# driver3.net
KiCad netlist of a schematic drawn in EAGLE
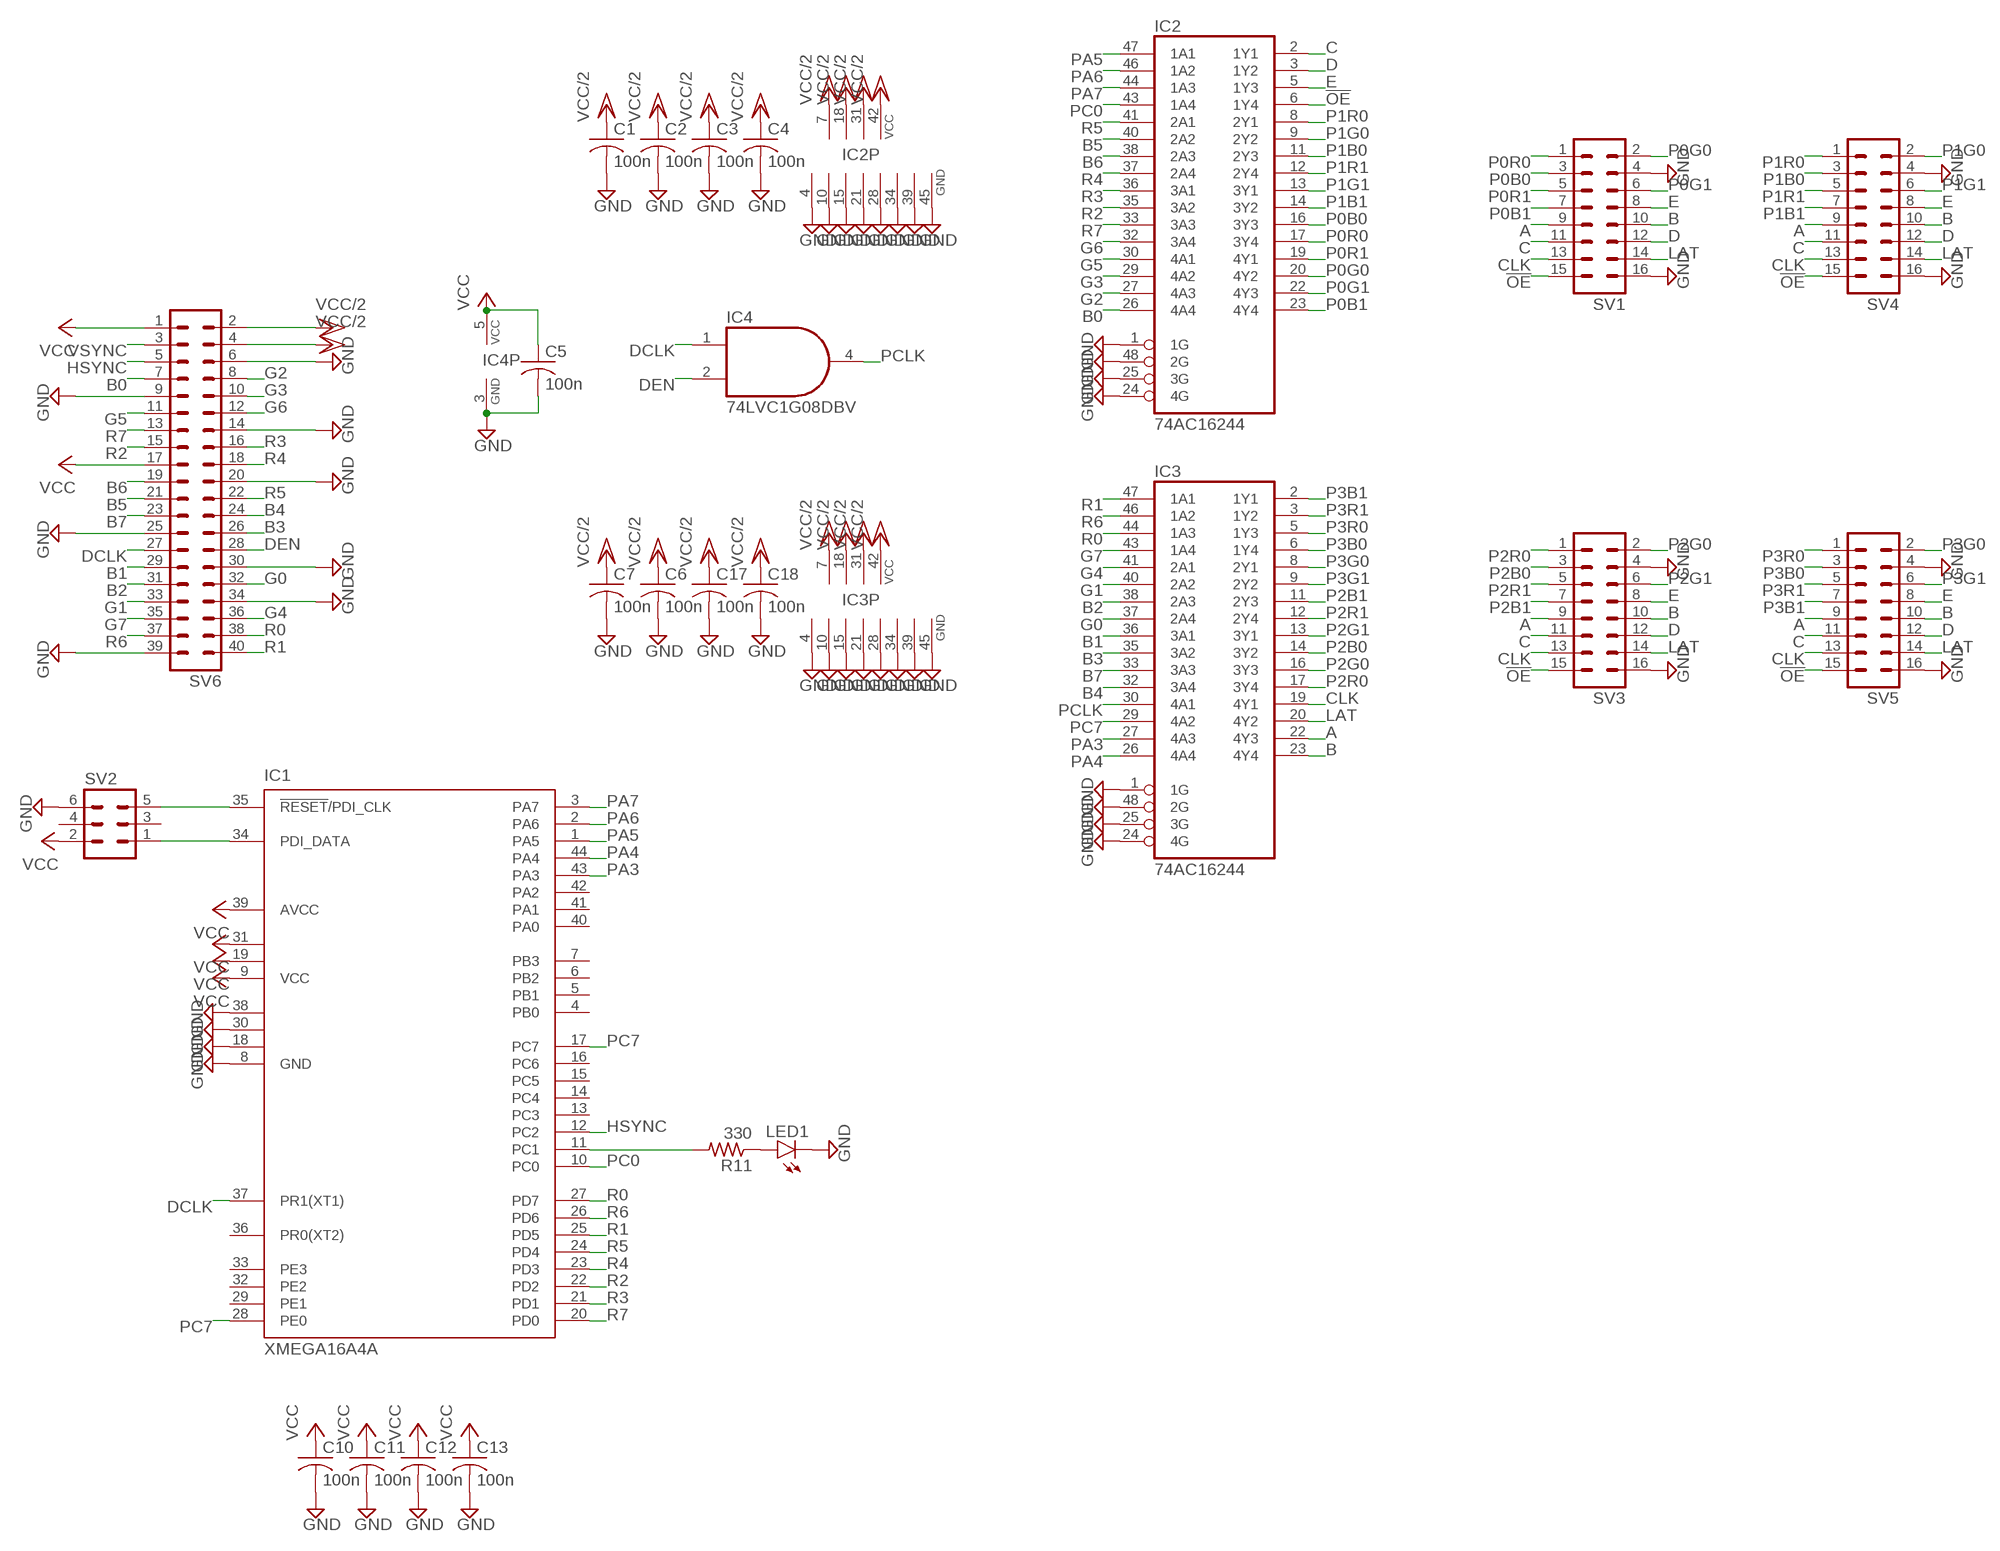
[diagram p0: schematic, sheet 1]

(export (version "E")
  (design (tool "Eeschema 10.0.6"))
  (components
    (comp (ref "C1")
      (value "100n")
      (footprint "eagle-import:C0402")
      (libsource (lib "eagle-import") (part "C-USC0402"))
    )
    (comp (ref "C2")
      (value "100n")
      (footprint "eagle-import:C0402")
      (libsource (lib "eagle-import") (part "C-USC0402"))
    )
    (comp (ref "C3")
      (value "100n")
      (footprint "eagle-import:C0402")
      (libsource (lib "eagle-import") (part "C-USC0402"))
    )
    (comp (ref "C4")
      (value "100n")
      (footprint "eagle-import:C0402")
      (libsource (lib "eagle-import") (part "C-USC0402"))
    )
    (comp (ref "C5")
      (value "100n")
      (footprint "eagle-import:C0402")
      (libsource (lib "eagle-import") (part "C-USC0402"))
    )
    (comp (ref "C6")
      (value "100n")
      (footprint "eagle-import:C0402")
      (libsource (lib "eagle-import") (part "C-USC0402"))
    )
    (comp (ref "C7")
      (value "100n")
      (footprint "eagle-import:C0402")
      (libsource (lib "eagle-import") (part "C-USC0402"))
    )
    (comp (ref "C10")
      (value "100n")
      (footprint "eagle-import:C0402")
      (libsource (lib "eagle-import") (part "C-USC0402"))
    )
    (comp (ref "C11")
      (value "100n")
      (footprint "eagle-import:C0402")
      (libsource (lib "eagle-import") (part "C-USC0402"))
    )
    (comp (ref "C12")
      (value "100n")
      (footprint "eagle-import:C0402")
      (libsource (lib "eagle-import") (part "C-USC0402"))
    )
    (comp (ref "C13")
      (value "100n")
      (footprint "eagle-import:C0402")
      (libsource (lib "eagle-import") (part "C-USC0402"))
    )
    (comp (ref "C17")
      (value "100n")
      (footprint "eagle-import:C0402")
      (libsource (lib "eagle-import") (part "C-USC0402"))
    )
    (comp (ref "C18")
      (value "100n")
      (footprint "eagle-import:C0402")
      (libsource (lib "eagle-import") (part "C-USC0402"))
    )
    (comp (ref "IC1")
      (value "XMEGA16A4A")
      (footprint "eagle-import:TQFP44")
      (libsource (lib "eagle-import") (part "XMEGA16A4A"))
    )
    (comp (ref "IC2")
      (value "74AC16244")
      (footprint "eagle-import:SSOP48DL")
      (libsource (lib "eagle-import") (part "74AC16244"))
    )
    (comp (ref "IC3")
      (value "74AC16244")
      (footprint "eagle-import:SSOP48DL")
      (libsource (lib "eagle-import") (part "74AC16244"))
    )
    (comp (ref "IC4")
      (value "74LVC1G08DBV")
      (footprint "eagle-import:SOT23-5")
      (libsource (lib "eagle-import") (part "741G08DBVLVC"))
    )
    (comp (ref "LED1")
      (value "LEDCHIPLED_0805")
      (footprint "eagle-import:CHIPLED_0805")
      (libsource (lib "eagle-import") (part "LEDCHIPLED_0805"))
    )
    (comp (ref "R11")
      (value "330")
      (footprint "eagle-import:R0402")
      (libsource (lib "eagle-import") (part "R-US_R0402"))
    )
    (comp (ref "SV1")
      (value "MA08-2")
      (footprint "eagle-import:MA08-2")
      (libsource (lib "eagle-import") (part "MA08-2"))
    )
    (comp (ref "SV2")
      (value "MA03-2")
      (footprint "eagle-import:MA03-2")
      (libsource (lib "eagle-import") (part "MA03-2"))
    )
    (comp (ref "SV3")
      (value "MA08-2")
      (footprint "eagle-import:MA08-2")
      (libsource (lib "eagle-import") (part "MA08-2"))
    )
    (comp (ref "SV4")
      (value "MA08-2")
      (footprint "eagle-import:MA08-2")
      (libsource (lib "eagle-import") (part "MA08-2"))
    )
    (comp (ref "SV5")
      (value "MA08-2")
      (footprint "eagle-import:MA08-2")
      (libsource (lib "eagle-import") (part "MA08-2"))
    )
    (comp (ref "SV6")
      (value "MA20-2")
      (footprint "eagle-import:MA20-2")
      (libsource (lib "eagle-import") (part "MA20-2"))
    )
  )
  (nets
    (net (code "1") (name "/A") (class "Default")
      (node (ref "IC3") (pin "22") (pinfunction "4Y3_22") (pintype "tri_state"))
      (node (ref "SV1") (pin "9") (pinfunction "9_9") (pintype "passive"))
      (node (ref "SV3") (pin "9") (pinfunction "9_9") (pintype "passive"))
      (node (ref "SV4") (pin "9") (pinfunction "9_9") (pintype "passive"))
      (node (ref "SV5") (pin "9") (pinfunction "9_9") (pintype "passive"))
    )
    (net (code "2") (name "/B") (class "Default")
      (node (ref "IC3") (pin "23") (pinfunction "4Y4_23") (pintype "tri_state"))
      (node (ref "SV1") (pin "10") (pinfunction "10_10") (pintype "passive"))
      (node (ref "SV3") (pin "10") (pinfunction "10_10") (pintype "passive"))
      (node (ref "SV4") (pin "10") (pinfunction "10_10") (pintype "passive"))
      (node (ref "SV5") (pin "10") (pinfunction "10_10") (pintype "passive"))
    )
    (net (code "3") (name "/B0") (class "Default")
      (node (ref "IC2") (pin "26") (pinfunction "4A4_26") (pintype "input"))
      (node (ref "SV6") (pin "7") (pinfunction "7_7") (pintype "passive"))
    )
    (net (code "4") (name "/B1") (class "Default")
      (node (ref "IC3") (pin "36") (pinfunction "3A1_36") (pintype "input"))
      (node (ref "SV6") (pin "29") (pinfunction "29_29") (pintype "passive"))
    )
    (net (code "5") (name "/B2") (class "Default")
      (node (ref "IC3") (pin "38") (pinfunction "2A3_38") (pintype "input"))
      (node (ref "SV6") (pin "31") (pinfunction "31_31") (pintype "passive"))
    )
    (net (code "6") (name "/B3") (class "Default")
      (node (ref "IC3") (pin "35") (pinfunction "3A2_35") (pintype "input"))
      (node (ref "SV6") (pin "26") (pinfunction "26_26") (pintype "passive"))
    )
    (net (code "7") (name "/B4") (class "Default")
      (node (ref "IC3") (pin "32") (pinfunction "3A4_32") (pintype "input"))
      (node (ref "SV6") (pin "24") (pinfunction "24_24") (pintype "passive"))
    )
    (net (code "8") (name "/B5") (class "Default")
      (node (ref "IC2") (pin "40") (pinfunction "2A2_40") (pintype "input"))
      (node (ref "SV6") (pin "21") (pinfunction "21_21") (pintype "passive"))
    )
    (net (code "9") (name "/B6") (class "Default")
      (node (ref "IC2") (pin "38") (pinfunction "2A3_38") (pintype "input"))
      (node (ref "SV6") (pin "19") (pinfunction "19_19") (pintype "passive"))
    )
    (net (code "10") (name "/B7") (class "Default")
      (node (ref "IC3") (pin "33") (pinfunction "3A3_33") (pintype "input"))
      (node (ref "SV6") (pin "23") (pinfunction "23_23") (pintype "passive"))
    )
    (net (code "11") (name "/C") (class "Default")
      (node (ref "IC2") (pin "2") (pinfunction "1Y1_2") (pintype "tri_state"))
      (node (ref "SV1") (pin "11") (pinfunction "11_11") (pintype "passive"))
      (node (ref "SV3") (pin "11") (pinfunction "11_11") (pintype "passive"))
      (node (ref "SV4") (pin "11") (pinfunction "11_11") (pintype "passive"))
      (node (ref "SV5") (pin "11") (pinfunction "11_11") (pintype "passive"))
    )
    (net (code "12") (name "/CLK") (class "Default")
      (node (ref "IC3") (pin "19") (pinfunction "4Y1_19") (pintype "tri_state"))
      (node (ref "SV1") (pin "13") (pinfunction "13_13") (pintype "passive"))
      (node (ref "SV3") (pin "13") (pinfunction "13_13") (pintype "passive"))
      (node (ref "SV4") (pin "13") (pinfunction "13_13") (pintype "passive"))
      (node (ref "SV5") (pin "13") (pinfunction "13_13") (pintype "passive"))
    )
    (net (code "13") (name "/D") (class "Default")
      (node (ref "IC2") (pin "3") (pinfunction "1Y2_3") (pintype "tri_state"))
      (node (ref "SV1") (pin "12") (pinfunction "12_12") (pintype "passive"))
      (node (ref "SV3") (pin "12") (pinfunction "12_12") (pintype "passive"))
      (node (ref "SV4") (pin "12") (pinfunction "12_12") (pintype "passive"))
      (node (ref "SV5") (pin "12") (pinfunction "12_12") (pintype "passive"))
    )
    (net (code "14") (name "/DCLK") (class "Default")
      (node (ref "IC1") (pin "37") (pinfunction "PR1(XT1)_37") (pintype "bidirectional"))
      (node (ref "IC4") (pin "1") (pinfunction "I0_1") (pintype "input"))
      (node (ref "SV6") (pin "27") (pinfunction "27_27") (pintype "passive"))
    )
    (net (code "15") (name "/DEN") (class "Default")
      (node (ref "IC4") (pin "2") (pinfunction "I1_2") (pintype "input"))
      (node (ref "SV6") (pin "28") (pinfunction "28_28") (pintype "passive"))
    )
    (net (code "16") (name "/E") (class "Default")
      (node (ref "IC2") (pin "5") (pinfunction "1Y3_5") (pintype "tri_state"))
      (node (ref "SV1") (pin "8") (pinfunction "8_8") (pintype "passive"))
      (node (ref "SV3") (pin "8") (pinfunction "8_8") (pintype "passive"))
      (node (ref "SV4") (pin "8") (pinfunction "8_8") (pintype "passive"))
      (node (ref "SV5") (pin "8") (pinfunction "8_8") (pintype "passive"))
    )
    (net (code "17") (name "/G0") (class "Default")
      (node (ref "IC3") (pin "37") (pinfunction "2A4_37") (pintype "input"))
      (node (ref "SV6") (pin "32") (pinfunction "32_32") (pintype "passive"))
    )
    (net (code "18") (name "/G1") (class "Default")
      (node (ref "IC3") (pin "40") (pinfunction "2A2_40") (pintype "input"))
      (node (ref "SV6") (pin "33") (pinfunction "33_33") (pintype "passive"))
    )
    (net (code "19") (name "/G2") (class "Default")
      (node (ref "IC2") (pin "27") (pinfunction "4A3_27") (pintype "input"))
      (node (ref "SV6") (pin "8") (pinfunction "8_8") (pintype "passive"))
    )
    (net (code "20") (name "/G3") (class "Default")
      (node (ref "IC2") (pin "29") (pinfunction "4A2_29") (pintype "input"))
      (node (ref "SV6") (pin "10") (pinfunction "10_10") (pintype "passive"))
    )
    (net (code "21") (name "/G4") (class "Default")
      (node (ref "IC3") (pin "41") (pinfunction "2A1_41") (pintype "input"))
      (node (ref "SV6") (pin "36") (pinfunction "36_36") (pintype "passive"))
    )
    (net (code "22") (name "/G5") (class "Default")
      (node (ref "IC2") (pin "30") (pinfunction "4A1_30") (pintype "input"))
      (node (ref "SV6") (pin "11") (pinfunction "11_11") (pintype "passive"))
    )
    (net (code "23") (name "/G6") (class "Default")
      (node (ref "IC2") (pin "32") (pinfunction "3A4_32") (pintype "input"))
      (node (ref "SV6") (pin "12") (pinfunction "12_12") (pintype "passive"))
    )
    (net (code "24") (name "/G7") (class "Default")
      (node (ref "IC3") (pin "43") (pinfunction "1A4_43") (pintype "input"))
      (node (ref "SV6") (pin "35") (pinfunction "35_35") (pintype "passive"))
    )
    (net (code "25") (name "/HSYNC") (class "Default")
      (node (ref "IC1") (pin "12") (pinfunction "PC2_12") (pintype "bidirectional"))
      (node (ref "SV6") (pin "5") (pinfunction "5_5") (pintype "passive"))
    )
    (net (code "26") (name "/LAT") (class "Default")
      (node (ref "IC3") (pin "20") (pinfunction "4Y2_20") (pintype "tri_state"))
      (node (ref "SV1") (pin "14") (pinfunction "14_14") (pintype "passive"))
      (node (ref "SV3") (pin "14") (pinfunction "14_14") (pintype "passive"))
      (node (ref "SV4") (pin "14") (pinfunction "14_14") (pintype "passive"))
      (node (ref "SV5") (pin "14") (pinfunction "14_14") (pintype "passive"))
    )
    (net (code "27") (name "/P0B0") (class "Default")
      (node (ref "IC2") (pin "16") (pinfunction "3Y3_16") (pintype "tri_state"))
      (node (ref "SV1") (pin "3") (pinfunction "3_3") (pintype "passive"))
    )
    (net (code "28") (name "/P0B1") (class "Default")
      (node (ref "IC2") (pin "23") (pinfunction "4Y4_23") (pintype "tri_state"))
      (node (ref "SV1") (pin "7") (pinfunction "7_7") (pintype "passive"))
    )
    (net (code "29") (name "/P0G0") (class "Default")
      (node (ref "IC2") (pin "20") (pinfunction "4Y2_20") (pintype "tri_state"))
      (node (ref "SV1") (pin "2") (pinfunction "2_2") (pintype "passive"))
    )
    (net (code "30") (name "/P0G1") (class "Default")
      (node (ref "IC2") (pin "22") (pinfunction "4Y3_22") (pintype "tri_state"))
      (node (ref "SV1") (pin "6") (pinfunction "6_6") (pintype "passive"))
    )
    (net (code "31") (name "/P0R0") (class "Default")
      (node (ref "IC2") (pin "17") (pinfunction "3Y4_17") (pintype "tri_state"))
      (node (ref "SV1") (pin "1") (pinfunction "1_1") (pintype "passive"))
    )
    (net (code "32") (name "/P0R1") (class "Default")
      (node (ref "IC2") (pin "19") (pinfunction "4Y1_19") (pintype "tri_state"))
      (node (ref "SV1") (pin "5") (pinfunction "5_5") (pintype "passive"))
    )
    (net (code "33") (name "/P1B0") (class "Default")
      (node (ref "IC2") (pin "11") (pinfunction "2Y3_11") (pintype "tri_state"))
      (node (ref "SV4") (pin "3") (pinfunction "3_3") (pintype "passive"))
    )
    (net (code "34") (name "/P1B1") (class "Default")
      (node (ref "IC2") (pin "14") (pinfunction "3Y2_14") (pintype "tri_state"))
      (node (ref "SV4") (pin "7") (pinfunction "7_7") (pintype "passive"))
    )
    (net (code "35") (name "/P1G0") (class "Default")
      (node (ref "IC2") (pin "9") (pinfunction "2Y2_9") (pintype "tri_state"))
      (node (ref "SV4") (pin "2") (pinfunction "2_2") (pintype "passive"))
    )
    (net (code "36") (name "/P1G1") (class "Default")
      (node (ref "IC2") (pin "13") (pinfunction "3Y1_13") (pintype "tri_state"))
      (node (ref "SV4") (pin "6") (pinfunction "6_6") (pintype "passive"))
    )
    (net (code "37") (name "/P1R0") (class "Default")
      (node (ref "IC2") (pin "8") (pinfunction "2Y1_8") (pintype "tri_state"))
      (node (ref "SV4") (pin "1") (pinfunction "1_1") (pintype "passive"))
    )
    (net (code "38") (name "/P1R1") (class "Default")
      (node (ref "IC2") (pin "12") (pinfunction "2Y4_12") (pintype "tri_state"))
      (node (ref "SV4") (pin "5") (pinfunction "5_5") (pintype "passive"))
    )
    (net (code "39") (name "/P2B0") (class "Default")
      (node (ref "IC3") (pin "14") (pinfunction "3Y2_14") (pintype "tri_state"))
      (node (ref "SV3") (pin "3") (pinfunction "3_3") (pintype "passive"))
    )
    (net (code "40") (name "/P2B1") (class "Default")
      (node (ref "IC3") (pin "11") (pinfunction "2Y3_11") (pintype "tri_state"))
      (node (ref "SV3") (pin "7") (pinfunction "7_7") (pintype "passive"))
    )
    (net (code "41") (name "/P2G0") (class "Default")
      (node (ref "IC3") (pin "16") (pinfunction "3Y3_16") (pintype "tri_state"))
      (node (ref "SV3") (pin "2") (pinfunction "2_2") (pintype "passive"))
    )
    (net (code "42") (name "/P2G1") (class "Default")
      (node (ref "IC3") (pin "13") (pinfunction "3Y1_13") (pintype "tri_state"))
      (node (ref "SV3") (pin "6") (pinfunction "6_6") (pintype "passive"))
    )
    (net (code "43") (name "/P2R0") (class "Default")
      (node (ref "IC3") (pin "17") (pinfunction "3Y4_17") (pintype "tri_state"))
      (node (ref "SV3") (pin "1") (pinfunction "1_1") (pintype "passive"))
    )
    (net (code "44") (name "/P2R1") (class "Default")
      (node (ref "IC3") (pin "12") (pinfunction "2Y4_12") (pintype "tri_state"))
      (node (ref "SV3") (pin "5") (pinfunction "5_5") (pintype "passive"))
    )
    (net (code "45") (name "/P3B0") (class "Default")
      (node (ref "IC3") (pin "6") (pinfunction "1Y4_6") (pintype "tri_state"))
      (node (ref "SV5") (pin "3") (pinfunction "3_3") (pintype "passive"))
    )
    (net (code "46") (name "/P3B1") (class "Default")
      (node (ref "IC3") (pin "2") (pinfunction "1Y1_2") (pintype "tri_state"))
      (node (ref "SV5") (pin "7") (pinfunction "7_7") (pintype "passive"))
    )
    (net (code "47") (name "/P3G0") (class "Default")
      (node (ref "IC3") (pin "8") (pinfunction "2Y1_8") (pintype "tri_state"))
      (node (ref "SV5") (pin "2") (pinfunction "2_2") (pintype "passive"))
    )
    (net (code "48") (name "/P3G1") (class "Default")
      (node (ref "IC3") (pin "9") (pinfunction "2Y2_9") (pintype "tri_state"))
      (node (ref "SV5") (pin "6") (pinfunction "6_6") (pintype "passive"))
    )
    (net (code "49") (name "/P3R0") (class "Default")
      (node (ref "IC3") (pin "5") (pinfunction "1Y3_5") (pintype "tri_state"))
      (node (ref "SV5") (pin "1") (pinfunction "1_1") (pintype "passive"))
    )
    (net (code "50") (name "/P3R1") (class "Default")
      (node (ref "IC3") (pin "3") (pinfunction "1Y2_3") (pintype "tri_state"))
      (node (ref "SV5") (pin "5") (pinfunction "5_5") (pintype "passive"))
    )
    (net (code "51") (name "/PA3") (class "Default")
      (node (ref "IC1") (pin "43") (pinfunction "PA3_43") (pintype "bidirectional"))
      (node (ref "IC3") (pin "27") (pinfunction "4A3_27") (pintype "input"))
    )
    (net (code "52") (name "/PA4") (class "Default")
      (node (ref "IC1") (pin "44") (pinfunction "PA4_44") (pintype "bidirectional"))
      (node (ref "IC3") (pin "26") (pinfunction "4A4_26") (pintype "input"))
    )
    (net (code "53") (name "/PA5") (class "Default")
      (node (ref "IC1") (pin "1") (pinfunction "PA5_1") (pintype "bidirectional"))
      (node (ref "IC2") (pin "47") (pinfunction "1A1_47") (pintype "input"))
    )
    (net (code "54") (name "/PA6") (class "Default")
      (node (ref "IC1") (pin "2") (pinfunction "PA6_2") (pintype "bidirectional"))
      (node (ref "IC2") (pin "46") (pinfunction "1A2_46") (pintype "input"))
    )
    (net (code "55") (name "/PA7") (class "Default")
      (node (ref "IC1") (pin "3") (pinfunction "PA7_3") (pintype "bidirectional"))
      (node (ref "IC2") (pin "44") (pinfunction "1A3_44") (pintype "input"))
    )
    (net (code "56") (name "/PC0") (class "Default")
      (node (ref "IC1") (pin "10") (pinfunction "PC0_10") (pintype "bidirectional"))
      (node (ref "IC2") (pin "43") (pinfunction "1A4_43") (pintype "input"))
    )
    (net (code "57") (name "/PC7") (class "Default")
      (node (ref "IC1") (pin "17") (pinfunction "PC7_17") (pintype "bidirectional"))
      (node (ref "IC1") (pin "28") (pinfunction "PE0_28") (pintype "bidirectional"))
      (node (ref "IC3") (pin "29") (pinfunction "4A2_29") (pintype "input"))
    )
    (net (code "58") (name "/PCLK") (class "Default")
      (node (ref "IC3") (pin "30") (pinfunction "4A1_30") (pintype "input"))
      (node (ref "IC4") (pin "4") (pinfunction "O_4") (pintype "output"))
    )
    (net (code "59") (name "/R0") (class "Default")
      (node (ref "IC1") (pin "27") (pinfunction "PD7_27") (pintype "bidirectional"))
      (node (ref "IC3") (pin "44") (pinfunction "1A3_44") (pintype "input"))
      (node (ref "SV6") (pin "38") (pinfunction "38_38") (pintype "passive"))
    )
    (net (code "60") (name "/R1") (class "Default")
      (node (ref "IC1") (pin "25") (pinfunction "PD5_25") (pintype "bidirectional"))
      (node (ref "IC3") (pin "47") (pinfunction "1A1_47") (pintype "input"))
      (node (ref "SV6") (pin "40") (pinfunction "40_40") (pintype "passive"))
    )
    (net (code "61") (name "/R2") (class "Default")
      (node (ref "IC1") (pin "22") (pinfunction "PD2_22") (pintype "bidirectional"))
      (node (ref "IC2") (pin "35") (pinfunction "3A2_35") (pintype "input"))
      (node (ref "SV6") (pin "15") (pinfunction "15_15") (pintype "passive"))
    )
    (net (code "62") (name "/R3") (class "Default")
      (node (ref "IC1") (pin "21") (pinfunction "PD1_21") (pintype "bidirectional"))
      (node (ref "IC2") (pin "36") (pinfunction "3A1_36") (pintype "input"))
      (node (ref "SV6") (pin "16") (pinfunction "16_16") (pintype "passive"))
    )
    (net (code "63") (name "/R4") (class "Default")
      (node (ref "IC1") (pin "23") (pinfunction "PD3_23") (pintype "bidirectional"))
      (node (ref "IC2") (pin "37") (pinfunction "2A4_37") (pintype "input"))
      (node (ref "SV6") (pin "18") (pinfunction "18_18") (pintype "passive"))
    )
    (net (code "64") (name "/R5") (class "Default")
      (node (ref "IC1") (pin "24") (pinfunction "PD4_24") (pintype "bidirectional"))
      (node (ref "IC2") (pin "41") (pinfunction "2A1_41") (pintype "input"))
      (node (ref "SV6") (pin "22") (pinfunction "22_22") (pintype "passive"))
    )
    (net (code "65") (name "/R6") (class "Default")
      (node (ref "IC1") (pin "26") (pinfunction "PD6_26") (pintype "bidirectional"))
      (node (ref "IC3") (pin "46") (pinfunction "1A2_46") (pintype "input"))
      (node (ref "SV6") (pin "37") (pinfunction "37_37") (pintype "passive"))
    )
    (net (code "66") (name "/R7") (class "Default")
      (node (ref "IC1") (pin "20") (pinfunction "PD0_20") (pintype "bidirectional"))
      (node (ref "IC2") (pin "33") (pinfunction "3A3_33") (pintype "input"))
      (node (ref "SV6") (pin "13") (pinfunction "13_13") (pintype "passive"))
    )
    (net (code "67") (name "/VSYNC") (class "Default")
      (node (ref "SV6") (pin "3") (pinfunction "3_3") (pintype "passive"))
    )
    (net (code "68") (name "/~{OE}") (class "Default")
      (node (ref "IC2") (pin "6") (pinfunction "1Y4_6") (pintype "tri_state"))
      (node (ref "SV1") (pin "15") (pinfunction "15_15") (pintype "passive"))
      (node (ref "SV3") (pin "15") (pinfunction "15_15") (pintype "passive"))
      (node (ref "SV4") (pin "15") (pinfunction "15_15") (pintype "passive"))
      (node (ref "SV5") (pin "15") (pinfunction "15_15") (pintype "passive"))
    )
    (net (code "69") (name "GND") (class "Default")
      (node (ref "C1") (pin "2") (pinfunction "2_2") (pintype "passive"))
      (node (ref "C10") (pin "2") (pinfunction "2_2") (pintype "passive"))
      (node (ref "C11") (pin "2") (pinfunction "2_2") (pintype "passive"))
      (node (ref "C12") (pin "2") (pinfunction "2_2") (pintype "passive"))
      (node (ref "C13") (pin "2") (pinfunction "2_2") (pintype "passive"))
      (node (ref "C17") (pin "2") (pinfunction "2_2") (pintype "passive"))
      (node (ref "C18") (pin "2") (pinfunction "2_2") (pintype "passive"))
      (node (ref "C2") (pin "2") (pinfunction "2_2") (pintype "passive"))
      (node (ref "C3") (pin "2") (pinfunction "2_2") (pintype "passive"))
      (node (ref "C4") (pin "2") (pinfunction "2_2") (pintype "passive"))
      (node (ref "C5") (pin "2") (pinfunction "2_2") (pintype "passive"))
      (node (ref "C6") (pin "2") (pinfunction "2_2") (pintype "passive"))
      (node (ref "C7") (pin "2") (pinfunction "2_2") (pintype "passive"))
      (node (ref "IC1") (pin "18") (pinfunction "GND1_18") (pintype "power_in"))
      (node (ref "IC1") (pin "30") (pinfunction "GND2_30") (pintype "power_in"))
      (node (ref "IC1") (pin "38") (pinfunction "GND3_38") (pintype "power_in"))
      (node (ref "IC1") (pin "8") (pinfunction "GND_8") (pintype "power_in"))
      (node (ref "IC2") (pin "1") (pinfunction "1G_1") (pintype "input"))
      (node (ref "IC2") (pin "10") (pinfunction "GND_10") (pintype "power_in"))
      (node (ref "IC2") (pin "15") (pinfunction "GND_15") (pintype "power_in"))
      (node (ref "IC2") (pin "21") (pinfunction "GND_21") (pintype "power_in"))
      (node (ref "IC2") (pin "24") (pinfunction "4G_24") (pintype "input"))
      (node (ref "IC2") (pin "25") (pinfunction "3G_25") (pintype "input"))
      (node (ref "IC2") (pin "28") (pinfunction "GND_28") (pintype "power_in"))
      (node (ref "IC2") (pin "34") (pinfunction "GND_34") (pintype "power_in"))
      (node (ref "IC2") (pin "39") (pinfunction "GND_39") (pintype "power_in"))
      (node (ref "IC2") (pin "4") (pinfunction "GND_4") (pintype "power_in"))
      (node (ref "IC2") (pin "45") (pinfunction "GND_45") (pintype "power_in"))
      (node (ref "IC2") (pin "48") (pinfunction "2G_48") (pintype "input"))
      (node (ref "IC3") (pin "1") (pinfunction "1G_1") (pintype "input"))
      (node (ref "IC3") (pin "10") (pinfunction "GND_10") (pintype "power_in"))
      (node (ref "IC3") (pin "15") (pinfunction "GND_15") (pintype "power_in"))
      (node (ref "IC3") (pin "21") (pinfunction "GND_21") (pintype "power_in"))
      (node (ref "IC3") (pin "24") (pinfunction "4G_24") (pintype "input"))
      (node (ref "IC3") (pin "25") (pinfunction "3G_25") (pintype "input"))
      (node (ref "IC3") (pin "28") (pinfunction "GND_28") (pintype "power_in"))
      (node (ref "IC3") (pin "34") (pinfunction "GND_34") (pintype "power_in"))
      (node (ref "IC3") (pin "39") (pinfunction "GND_39") (pintype "power_in"))
      (node (ref "IC3") (pin "4") (pinfunction "GND_4") (pintype "power_in"))
      (node (ref "IC3") (pin "45") (pinfunction "GND_45") (pintype "power_in"))
      (node (ref "IC3") (pin "48") (pinfunction "2G_48") (pintype "input"))
      (node (ref "IC4") (pin "3") (pinfunction "GND_3") (pintype "power_in"))
      (node (ref "LED1") (pin "C") (pinfunction "C_C") (pintype "passive"))
      (node (ref "SV1") (pin "16") (pinfunction "16_16") (pintype "passive"))
      (node (ref "SV1") (pin "4") (pinfunction "4_4") (pintype "passive"))
      (node (ref "SV2") (pin "6") (pinfunction "6_6") (pintype "passive"))
      (node (ref "SV3") (pin "16") (pinfunction "16_16") (pintype "passive"))
      (node (ref "SV3") (pin "4") (pinfunction "4_4") (pintype "passive"))
      (node (ref "SV4") (pin "16") (pinfunction "16_16") (pintype "passive"))
      (node (ref "SV4") (pin "4") (pinfunction "4_4") (pintype "passive"))
      (node (ref "SV5") (pin "16") (pinfunction "16_16") (pintype "passive"))
      (node (ref "SV5") (pin "4") (pinfunction "4_4") (pintype "passive"))
      (node (ref "SV6") (pin "14") (pinfunction "14_14") (pintype "passive"))
      (node (ref "SV6") (pin "20") (pinfunction "20_20") (pintype "passive"))
      (node (ref "SV6") (pin "25") (pinfunction "25_25") (pintype "passive"))
      (node (ref "SV6") (pin "30") (pinfunction "30_30") (pintype "passive"))
      (node (ref "SV6") (pin "34") (pinfunction "34_34") (pintype "passive"))
      (node (ref "SV6") (pin "39") (pinfunction "39_39") (pintype "passive"))
      (node (ref "SV6") (pin "6") (pinfunction "6_6") (pintype "passive"))
      (node (ref "SV6") (pin "9") (pinfunction "9_9") (pintype "passive"))
    )
    (net (code "70") (name "Net-(IC1-PC1)") (class "Default")
      (node (ref "IC1") (pin "11") (pinfunction "PC1_11") (pintype "bidirectional"))
      (node (ref "R11") (pin "2") (pinfunction "2_2") (pintype "passive"))
    )
    (net (code "71") (name "Net-(IC1-PDI_DATA)") (class "Default")
      (node (ref "IC1") (pin "34") (pinfunction "PDI_DATA_34") (pintype "bidirectional"))
      (node (ref "SV2") (pin "1") (pinfunction "1_1") (pintype "passive"))
    )
    (net (code "72") (name "Net-(IC1-~{RESET}{slash}PDI_CLK)") (class "Default")
      (node (ref "IC1") (pin "35") (pinfunction "~{RESET}/PDI_CLK_35") (pintype "bidirectional"))
      (node (ref "SV2") (pin "5") (pinfunction "5_5") (pintype "passive"))
    )
    (net (code "73") (name "Net-(LED1-PadA)") (class "Default")
      (node (ref "LED1") (pin "A") (pinfunction "A_A") (pintype "passive"))
      (node (ref "R11") (pin "1") (pinfunction "1_1") (pintype "passive"))
    )
    (net (code "74") (name "VCC") (class "Default")
      (node (ref "C10") (pin "1") (pinfunction "1_1") (pintype "passive"))
      (node (ref "C11") (pin "1") (pinfunction "1_1") (pintype "passive"))
      (node (ref "C12") (pin "1") (pinfunction "1_1") (pintype "passive"))
      (node (ref "C13") (pin "1") (pinfunction "1_1") (pintype "passive"))
      (node (ref "C5") (pin "1") (pinfunction "1_1") (pintype "passive"))
      (node (ref "IC1") (pin "19") (pinfunction "VCC1_19") (pintype "power_in"))
      (node (ref "IC1") (pin "31") (pinfunction "VCC2_31") (pintype "power_in"))
      (node (ref "IC1") (pin "39") (pinfunction "AVCC_39") (pintype "power_in"))
      (node (ref "IC1") (pin "9") (pinfunction "VCC_9") (pintype "power_in"))
      (node (ref "IC4") (pin "5") (pinfunction "VCC_5") (pintype "power_in"))
      (node (ref "SV2") (pin "2") (pinfunction "2_2") (pintype "passive"))
      (node (ref "SV6") (pin "1") (pinfunction "1_1") (pintype "passive"))
      (node (ref "SV6") (pin "17") (pinfunction "17_17") (pintype "passive"))
    )
    (net (code "75") (name "VCC{slash}2") (class "Default")
      (node (ref "C1") (pin "1") (pinfunction "1_1") (pintype "passive"))
      (node (ref "C17") (pin "1") (pinfunction "1_1") (pintype "passive"))
      (node (ref "C18") (pin "1") (pinfunction "1_1") (pintype "passive"))
      (node (ref "C2") (pin "1") (pinfunction "1_1") (pintype "passive"))
      (node (ref "C3") (pin "1") (pinfunction "1_1") (pintype "passive"))
      (node (ref "C4") (pin "1") (pinfunction "1_1") (pintype "passive"))
      (node (ref "C6") (pin "1") (pinfunction "1_1") (pintype "passive"))
      (node (ref "C7") (pin "1") (pinfunction "1_1") (pintype "passive"))
      (node (ref "IC2") (pin "18") (pinfunction "VCC_18") (pintype "power_in"))
      (node (ref "IC2") (pin "31") (pinfunction "VCC_31") (pintype "power_in"))
      (node (ref "IC2") (pin "42") (pinfunction "VCC_42") (pintype "power_in"))
      (node (ref "IC2") (pin "7") (pinfunction "VCC_7") (pintype "power_in"))
      (node (ref "IC3") (pin "18") (pinfunction "VCC_18") (pintype "power_in"))
      (node (ref "IC3") (pin "31") (pinfunction "VCC_31") (pintype "power_in"))
      (node (ref "IC3") (pin "42") (pinfunction "VCC_42") (pintype "power_in"))
      (node (ref "IC3") (pin "7") (pinfunction "VCC_7") (pintype "power_in"))
      (node (ref "SV6") (pin "2") (pinfunction "2_2") (pintype "passive"))
      (node (ref "SV6") (pin "4") (pinfunction "4_4") (pintype "passive"))
    )
    (net (code "76") (name "unconnected-(IC1-PA0-Pad40)") (class "Default")
      (node (ref "IC1") (pin "40") (pinfunction "PA0_40") (pintype "bidirectional"))
    )
    (net (code "77") (name "unconnected-(IC1-PA1-Pad41)") (class "Default")
      (node (ref "IC1") (pin "41") (pinfunction "PA1_41") (pintype "bidirectional"))
    )
    (net (code "78") (name "unconnected-(IC1-PA2-Pad42)") (class "Default")
      (node (ref "IC1") (pin "42") (pinfunction "PA2_42") (pintype "bidirectional"))
    )
    (net (code "79") (name "unconnected-(IC1-PB0-Pad4)") (class "Default")
      (node (ref "IC1") (pin "4") (pinfunction "PB0_4") (pintype "bidirectional"))
    )
    (net (code "80") (name "unconnected-(IC1-PB1-Pad5)") (class "Default")
      (node (ref "IC1") (pin "5") (pinfunction "PB1_5") (pintype "bidirectional"))
    )
    (net (code "81") (name "unconnected-(IC1-PB2-Pad6)") (class "Default")
      (node (ref "IC1") (pin "6") (pinfunction "PB2_6") (pintype "bidirectional"))
    )
    (net (code "82") (name "unconnected-(IC1-PB3-Pad7)") (class "Default")
      (node (ref "IC1") (pin "7") (pinfunction "PB3_7") (pintype "bidirectional"))
    )
    (net (code "83") (name "unconnected-(IC1-PC3-Pad13)") (class "Default")
      (node (ref "IC1") (pin "13") (pinfunction "PC3_13") (pintype "bidirectional"))
    )
    (net (code "84") (name "unconnected-(IC1-PC4-Pad14)") (class "Default")
      (node (ref "IC1") (pin "14") (pinfunction "PC4_14") (pintype "bidirectional"))
    )
    (net (code "85") (name "unconnected-(IC1-PC5-Pad15)") (class "Default")
      (node (ref "IC1") (pin "15") (pinfunction "PC5_15") (pintype "bidirectional"))
    )
    (net (code "86") (name "unconnected-(IC1-PC6-Pad16)") (class "Default")
      (node (ref "IC1") (pin "16") (pinfunction "PC6_16") (pintype "bidirectional"))
    )
    (net (code "87") (name "unconnected-(IC1-PE1-Pad29)") (class "Default")
      (node (ref "IC1") (pin "29") (pinfunction "PE1_29") (pintype "bidirectional"))
    )
    (net (code "88") (name "unconnected-(IC1-PE2-Pad32)") (class "Default")
      (node (ref "IC1") (pin "32") (pinfunction "PE2_32") (pintype "bidirectional"))
    )
    (net (code "89") (name "unconnected-(IC1-PE3-Pad33)") (class "Default")
      (node (ref "IC1") (pin "33") (pinfunction "PE3_33") (pintype "bidirectional"))
    )
    (net (code "90") (name "unconnected-(IC1-PR0(XT2)-Pad36)") (class "Default")
      (node (ref "IC1") (pin "36") (pinfunction "PR0(XT2)_36") (pintype "bidirectional"))
    )
    (net (code "91") (name "unconnected-(SV2-Pad3)") (class "Default")
      (node (ref "SV2") (pin "3") (pinfunction "3_3") (pintype "passive"))
    )
    (net (code "92") (name "unconnected-(SV2-Pad4)") (class "Default")
      (node (ref "SV2") (pin "4") (pinfunction "4_4") (pintype "passive"))
    )
  )
)
